# Escorna_CPU_2_10.net
KiCad netlist of a schematic drawn in EAGLE
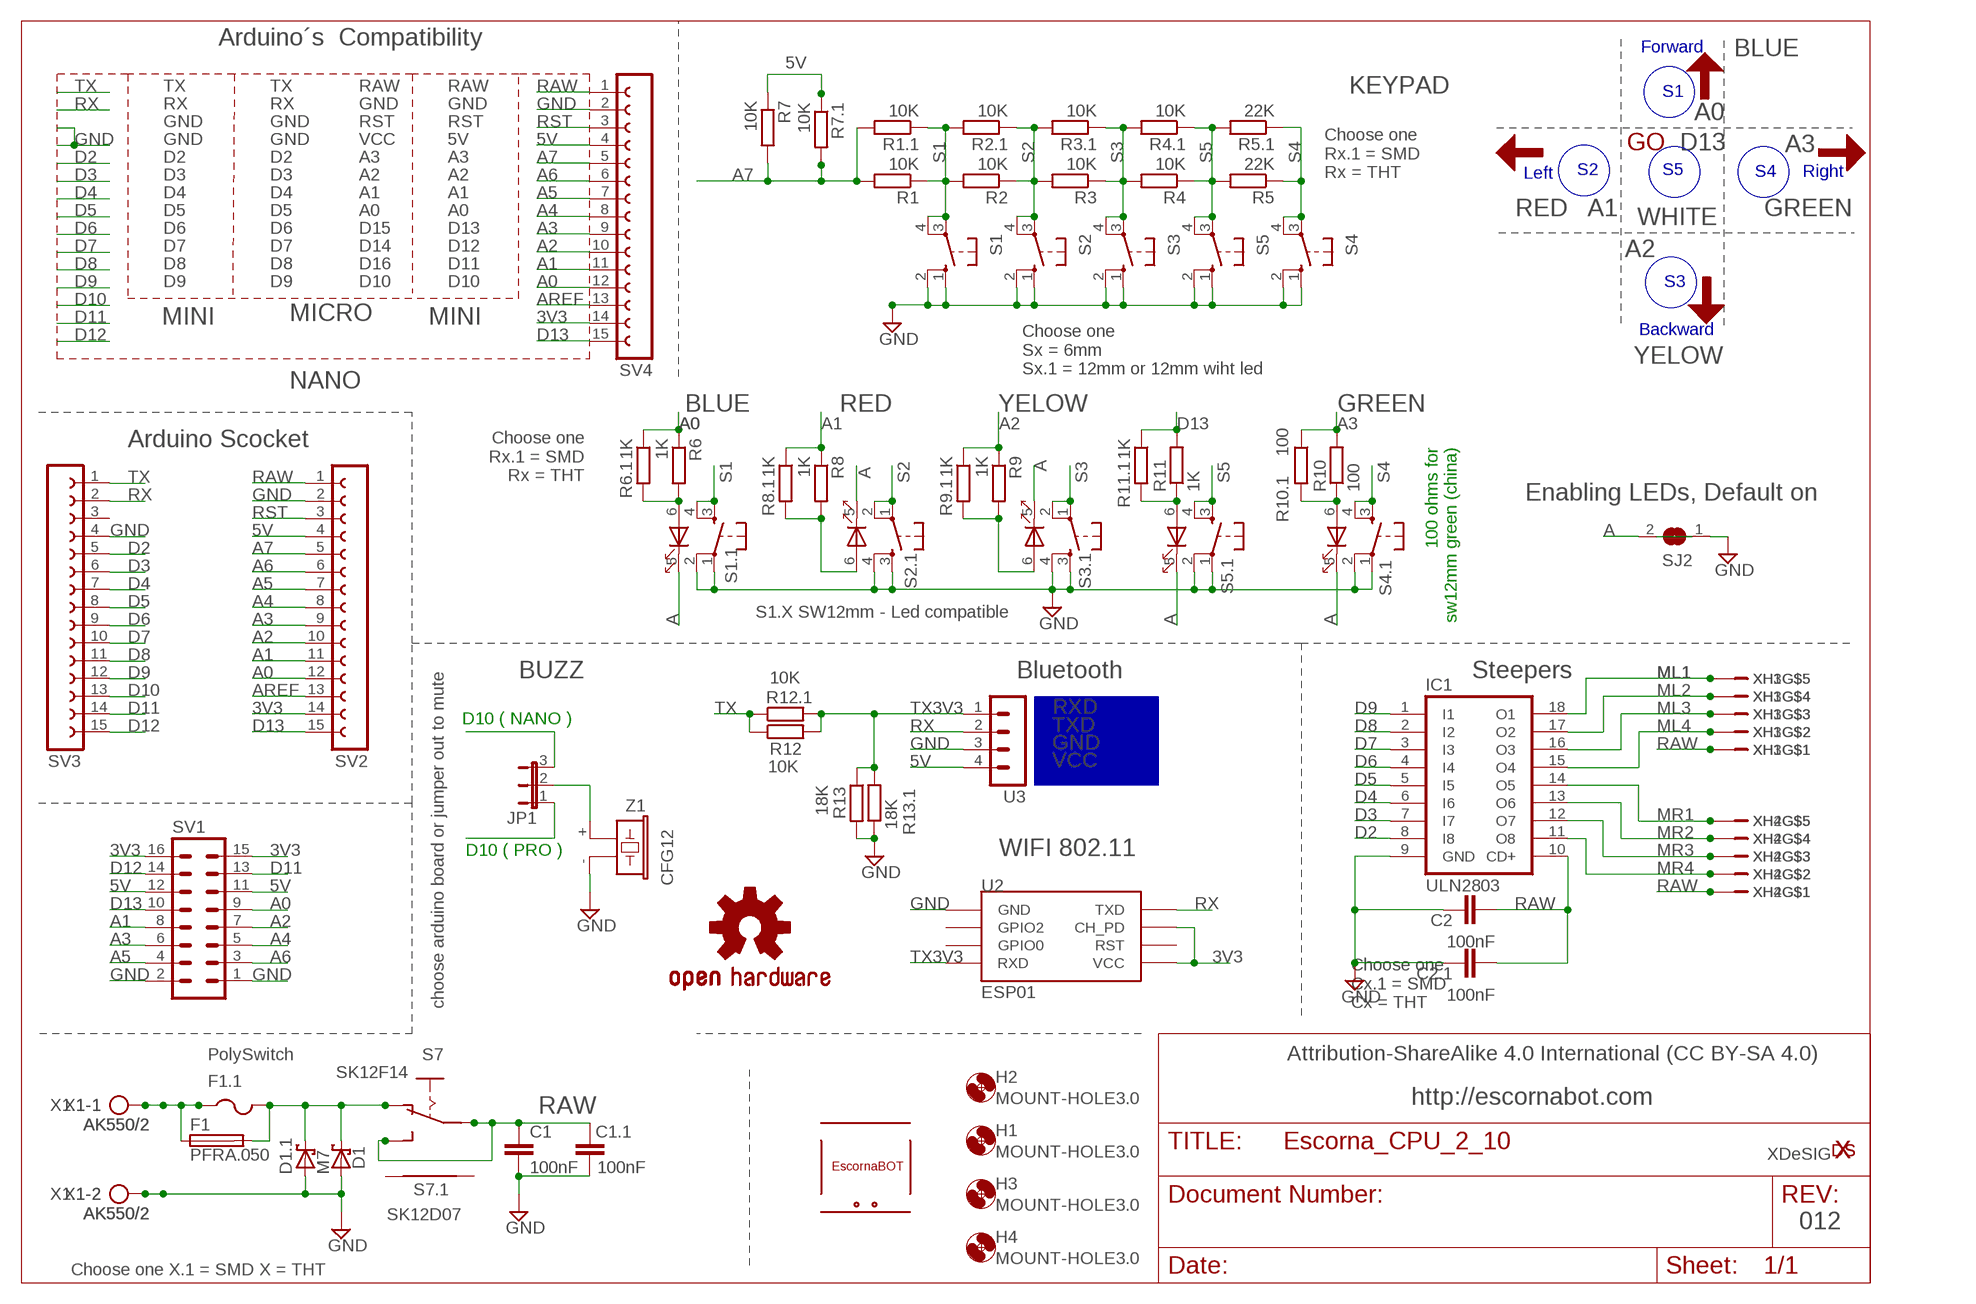
[diagram p0: schematic, sheet 1]

(export (version "E")
  (design (tool "Eeschema 10.0.6"))
  (components
    (comp (ref "C1")
      (value "100nF")
      (footprint "eagle-import:C025-025X050")
      (libsource (lib "eagle-import") (part "C-EU025-025X050"))
    )
    (comp (ref "C1.1")
      (value "100nF")
      (footprint "eagle-import:C1206")
      (libsource (lib "eagle-import") (part "C-EUC1206"))
    )
    (comp (ref "C2")
      (value "100nF")
      (footprint "eagle-import:C025-025X050")
      (libsource (lib "eagle-import") (part "C-EU025-025X050"))
    )
    (comp (ref "C2.1")
      (value "100nF")
      (footprint "eagle-import:C1206")
      (libsource (lib "eagle-import") (part "C-EUC1206"))
    )
    (comp (ref "D1")
      (value "1N5817")
      (footprint "eagle-import:DO41-10")
      (libsource (lib "eagle-import") (part "P4KEXX"))
    )
    (comp (ref "D1.1")
      (value "M7")
      (footprint "eagle-import:SMA")
      (libsource (lib "eagle-import") (part "SCHOTTKY-DIODESMA"))
    )
    (comp (ref "ESC")
      (value "ESCORNABOT")
      (footprint "eagle-import:ESCORNA_PEQUE")
      (libsource (lib "eagle-import") (part "ESCORNABOT"))
    )
    (comp (ref "F1")
      (value "PFRA.050")
      (footprint "eagle-import:TE5")
      (libsource (lib "eagle-import") (part "FUSETE5"))
    )
    (comp (ref "F1.1")
      (value "PolySwitch")
      (footprint "eagle-import:R1206")
      (libsource (lib "eagle-import") (part "PTCFUSE-1206"))
    )
    (comp (ref "H1")
      (value "MOUNT-HOLE3.0")
      (footprint "eagle-import:3,0")
      (libsource (lib "eagle-import") (part "MOUNT-HOLE3.0"))
    )
    (comp (ref "H2")
      (value "MOUNT-HOLE3.0")
      (footprint "eagle-import:3,0")
      (libsource (lib "eagle-import") (part "MOUNT-HOLE3.0"))
    )
    (comp (ref "H3")
      (value "MOUNT-HOLE3.0")
      (footprint "eagle-import:3,0")
      (libsource (lib "eagle-import") (part "MOUNT-HOLE3.0"))
    )
    (comp (ref "H4")
      (value "MOUNT-HOLE3.0")
      (footprint "eagle-import:3,0")
      (libsource (lib "eagle-import") (part "MOUNT-HOLE3.0"))
    )
    (comp (ref "IC1")
      (value "ULN2803")
      (footprint "eagle-import:DIL18")
      (libsource (lib "eagle-import") (part "ULN2803A"))
    )
    (comp (ref "JP1")
      (value "JUMPER_JP2E")
      (footprint "eagle-import:JUMPER_JP2")
      (libsource (lib "eagle-import") (part "JUMPER_JP2E"))
    )
    (comp (ref "LOGO2")
      (value "OSHW-LOGOS")
      (footprint "eagle-import:OSHW-LOGO-S")
      (libsource (lib "eagle-import") (part "OSHW-LOGOS"))
    )
    (comp (ref "R1")
      (value "10K")
      (footprint "eagle-import:0204_7")
      (libsource (lib "eagle-import") (part "R-EU_0204/7"))
    )
    (comp (ref "R1.1")
      (value "10K")
      (footprint "eagle-import:R0603")
      (libsource (lib "eagle-import") (part "R-EU_R0603"))
    )
    (comp (ref "R2")
      (value "10K")
      (footprint "eagle-import:0204_7")
      (libsource (lib "eagle-import") (part "R-EU_0204/7"))
    )
    (comp (ref "R2.1")
      (value "10K")
      (footprint "eagle-import:R0603")
      (libsource (lib "eagle-import") (part "R-EU_R0603"))
    )
    (comp (ref "R3")
      (value "10K")
      (footprint "eagle-import:0204_7")
      (libsource (lib "eagle-import") (part "R-EU_0204/7"))
    )
    (comp (ref "R3.1")
      (value "10K")
      (footprint "eagle-import:R0603")
      (libsource (lib "eagle-import") (part "R-EU_R0603"))
    )
    (comp (ref "R4")
      (value "10K")
      (footprint "eagle-import:0204_7")
      (libsource (lib "eagle-import") (part "R-EU_0204/7"))
    )
    (comp (ref "R4.1")
      (value "10K")
      (footprint "eagle-import:R0603")
      (libsource (lib "eagle-import") (part "R-EU_R0603"))
    )
    (comp (ref "R5")
      (value "22K")
      (footprint "eagle-import:0204_7")
      (libsource (lib "eagle-import") (part "R-EU_0204/7"))
    )
    (comp (ref "R5.1")
      (value "22K")
      (footprint "eagle-import:R0603")
      (libsource (lib "eagle-import") (part "R-EU_R0603"))
    )
    (comp (ref "R6")
      (value "1K")
      (footprint "eagle-import:0204_7")
      (libsource (lib "eagle-import") (part "R-EU_0204/7"))
    )
    (comp (ref "R6.1")
      (value "1K")
      (footprint "eagle-import:R0603")
      (libsource (lib "eagle-import") (part "R-EU_R0603"))
    )
    (comp (ref "R7")
      (value "10K")
      (footprint "eagle-import:0204_7")
      (libsource (lib "eagle-import") (part "R-EU_0204/7"))
    )
    (comp (ref "R7.1")
      (value "10K")
      (footprint "eagle-import:R0603")
      (libsource (lib "eagle-import") (part "R-EU_R0603"))
    )
    (comp (ref "R8")
      (value "1K")
      (footprint "eagle-import:0204_7")
      (libsource (lib "eagle-import") (part "R-EU_0204/7"))
    )
    (comp (ref "R8.1")
      (value "1K")
      (footprint "eagle-import:R0603")
      (libsource (lib "eagle-import") (part "R-EU_R0603"))
    )
    (comp (ref "R9")
      (value "1K")
      (footprint "eagle-import:0204_7")
      (libsource (lib "eagle-import") (part "R-EU_0204/7"))
    )
    (comp (ref "R9.1")
      (value "1K")
      (footprint "eagle-import:R0603")
      (libsource (lib "eagle-import") (part "R-EU_R0603"))
    )
    (comp (ref "R10")
      (value "100")
      (footprint "eagle-import:0204_7")
      (libsource (lib "eagle-import") (part "R-EU_0204/7"))
    )
    (comp (ref "R10.1")
      (value "100")
      (footprint "eagle-import:R0603")
      (libsource (lib "eagle-import") (part "R-EU_R0603"))
    )
    (comp (ref "R11")
      (value "1K")
      (footprint "eagle-import:0204_7")
      (libsource (lib "eagle-import") (part "R-EU_0204/7"))
    )
    (comp (ref "R11.1")
      (value "1K")
      (footprint "eagle-import:R0603")
      (libsource (lib "eagle-import") (part "R-EU_R0603"))
    )
    (comp (ref "R12")
      (value "10K")
      (footprint "eagle-import:0204_7")
      (libsource (lib "eagle-import") (part "R-EU_0204/7"))
    )
    (comp (ref "R12.1")
      (value "10K")
      (footprint "eagle-import:R0603")
      (libsource (lib "eagle-import") (part "R-EU_R0603"))
    )
    (comp (ref "R13")
      (value "18K")
      (footprint "eagle-import:0204_7")
      (libsource (lib "eagle-import") (part "R-EU_0204/7"))
    )
    (comp (ref "R13.1")
      (value "18K")
      (footprint "eagle-import:R0603")
      (libsource (lib "eagle-import") (part "R-EU_R0603"))
    )
    (comp (ref "S1")
      (value "10-XX")
      (footprint "eagle-import:B3F-10XX")
      (fields (field (name "MPN") "B3F-1000"))
      (libsource (lib "eagle-import") (part "10-XX"))
    )
    (comp (ref "S1.1")
      (value "B3F-9XXX")
      (footprint "eagle-import:B3F-9XXX")
      (libsource (lib "eagle-import") (part "SWITCH-OMRON_B3F-9XXX"))
    )
    (comp (ref "S2")
      (value "10-XX")
      (footprint "eagle-import:B3F-10XX")
      (fields (field (name "MPN") "B3F-1000"))
      (libsource (lib "eagle-import") (part "10-XX"))
    )
    (comp (ref "S2.1")
      (value "B3F-9XXX")
      (footprint "eagle-import:B3F-9XXX")
      (libsource (lib "eagle-import") (part "SWITCH-OMRON_B3F-9XXX"))
    )
    (comp (ref "S3")
      (value "10-XX")
      (footprint "eagle-import:B3F-10XX")
      (fields (field (name "MPN") "B3F-1000"))
      (libsource (lib "eagle-import") (part "10-XX"))
    )
    (comp (ref "S3.1")
      (value "B3F-9XXX")
      (footprint "eagle-import:B3F-9XXX")
      (libsource (lib "eagle-import") (part "SWITCH-OMRON_B3F-9XXX"))
    )
    (comp (ref "S4")
      (value "10-XX")
      (footprint "eagle-import:B3F-10XX")
      (fields (field (name "MPN") "B3F-1000"))
      (libsource (lib "eagle-import") (part "10-XX"))
    )
    (comp (ref "S4.1")
      (value "B3F-9XXX")
      (footprint "eagle-import:B3F-9XXX")
      (libsource (lib "eagle-import") (part "SWITCH-OMRON_B3F-9XXX"))
    )
    (comp (ref "S5")
      (value "10-XX")
      (footprint "eagle-import:B3F-10XX")
      (fields (field (name "MPN") "B3F-1000"))
      (libsource (lib "eagle-import") (part "10-XX"))
    )
    (comp (ref "S5.1")
      (value "B3F-9XXX")
      (footprint "eagle-import:B3F-9XXX")
      (libsource (lib "eagle-import") (part "SWITCH-OMRON_B3F-9XXX"))
    )
    (comp (ref "S7")
      (value "SK12F14")
      (footprint "eagle-import:ESCORNA_SK-12F14-G")
      (libsource (lib "eagle-import") (part "ESCORNA_SK12F14F"))
    )
    (comp (ref "S7.1")
      (value "SK12D07")
      (footprint "eagle-import:ESCORNA_SK-12D07")
      (libsource (lib "eagle-import") (part "ESCORNA_SK12F14D"))
    )
    (comp (ref "SJ2") (value "SJ") (footprint "eagle-import:SJ") (libsource (lib "eagle-import") (part "SJ")))
    (comp (ref "SV1")
      (value "MA08-2")
      (footprint "eagle-import:MA08-2")
      (libsource (lib "eagle-import") (part "MA08-2"))
    )
    (comp (ref "SV2")
      (value "CON-LSTA_FE15-1")
      (footprint "eagle-import:CON-LSTA_FE15")
      (libsource (lib "eagle-import") (part "CON-LSTA_FE15-1"))
    )
    (comp (ref "SV3")
      (value "CON-LSTA_FE15-1")
      (footprint "eagle-import:CON-LSTA_FE15")
      (libsource (lib "eagle-import") (part "CON-LSTA_FE15-1"))
    )
    (comp (ref "SV4")
      (value "CON-LSTA_FE15-1")
      (footprint "eagle-import:CON-LSTA_FE15")
      (fields (field (name "OC_FARNELL") "unknown") (field (name "OC_NEWARK") "unknown"))
      (libsource (lib "eagle-import") (part "CON-LSTA_FE15-1"))
    )
    (comp (ref "U$1")
      (value "FRECHA")
      (footprint "eagle-import:FRECHA")
      (libsource (lib "eagle-import") (part "FRECHA"))
    )
    (comp (ref "U$2")
      (value "GO")
      (footprint "eagle-import:VALE")
      (libsource (lib "eagle-import") (part "GO"))
    )
    (comp (ref "U$3")
      (value "FRECHA")
      (footprint "eagle-import:FRECHA")
      (libsource (lib "eagle-import") (part "FRECHA"))
    )
    (comp (ref "U$6")
      (value "FRECHA")
      (footprint "eagle-import:FRECHA")
      (libsource (lib "eagle-import") (part "FRECHA"))
    )
    (comp (ref "U$11")
      (value "FRECHA")
      (footprint "eagle-import:FRECHA")
      (libsource (lib "eagle-import") (part "FRECHA"))
    )
    (comp (ref "U$13")
      (value "XDESIG_XDESIG21")
      (footprint "eagle-import:XDESIG_XDESIG")
      (libsource (lib "eagle-import") (part "XDESIG_XDESIG21"))
    )
    (comp (ref "U2")
      (value "ESP01")
      (footprint "eagle-import:ESP01")
      (libsource (lib "eagle-import") (part "ESP01"))
    )
    (comp (ref "U3")
      (value "MA04-1")
      (footprint "eagle-import:MA04-1")
      (libsource (lib "eagle-import") (part "MA04-1"))
    )
    (comp (ref "X1")
      (value "AK550/2")
      (footprint "eagle-import:AK550_2")
      (libsource (lib "eagle-import") (part "AK550/2"))
    )
    (comp (ref "X1.1")
      (value "AK550/2")
      (footprint "eagle-import:AK550_2")
      (fields (field (name "OC_FARNELL") "unknown") (field (name "OC_NEWARK") "unknown"))
      (libsource (lib "eagle-import") (part "AK550/2"))
    )
    (comp (ref "XDS1")
      (value "XDESIG")
      (footprint "eagle-import:XDESIG_CU_2")
      (libsource (lib "eagle-import") (part "XDESIG"))
    )
    (comp (ref "XH1")
      (value "B5B-XH-A")
      (footprint "eagle-import:B5B-XH-A")
      (libsource (lib "eagle-import") (part "B5B-XH-A"))
    )
    (comp (ref "XH2")
      (value "B5B-XH-A")
      (footprint "eagle-import:B5B-XH-A")
      (libsource (lib "eagle-import") (part "B5B-XH-A"))
    )
    (comp (ref "XH3")
      (value "B5B-XH-A")
      (footprint "eagle-import:B5B-XH-A")
      (libsource (lib "eagle-import") (part "B5B-XH-A"))
    )
    (comp (ref "XH4")
      (value "B5B-XH-A")
      (footprint "eagle-import:B5B-XH-A")
      (libsource (lib "eagle-import") (part "B5B-XH-A"))
    )
    (comp (ref "Z1")
      (value "CFG12")
      (footprint "eagle-import:F_CM12P")
      (libsource (lib "eagle-import") (part "F/CM12P"))
    )
  )
  (nets
    (net (code "1") (name "/3V3") (class "Default")
      (node (ref "SV1") (pin "15") (pinfunction "15_15") (pintype "passive"))
      (node (ref "SV1") (pin "16") (pinfunction "16_16") (pintype "passive"))
      (node (ref "SV2") (pin "14") (pinfunction "14_14") (pintype "passive"))
      (node (ref "SV4") (pin "14") (pinfunction "14_14") (pintype "passive"))
      (node (ref "U2") (pin "CH_PD") (pinfunction "CH_PD_CH_PD") (pintype "bidirectional"))
      (node (ref "U2") (pin "VCC") (pinfunction "VCC_VCC") (pintype "bidirectional"))
    )
    (net (code "2") (name "/5V") (class "Default")
      (node (ref "R7") (pin "1") (pinfunction "1_1") (pintype "passive"))
      (node (ref "R7.1") (pin "1") (pinfunction "1_1") (pintype "passive"))
      (node (ref "SV1") (pin "11") (pinfunction "11_11") (pintype "passive"))
      (node (ref "SV1") (pin "12") (pinfunction "12_12") (pintype "passive"))
      (node (ref "SV2") (pin "4") (pinfunction "4_4") (pintype "passive"))
      (node (ref "SV4") (pin "4") (pinfunction "4_4") (pintype "passive"))
      (node (ref "U3") (pin "4") (pinfunction "4_4") (pintype "passive"))
    )
    (net (code "3") (name "/A") (class "Default")
      (node (ref "S1.1") (pin "5") (pinfunction "K_5") (pintype "passive"))
      (node (ref "S2.1") (pin "5") (pinfunction "K_5") (pintype "passive"))
      (node (ref "S3.1") (pin "5") (pinfunction "K_5") (pintype "passive"))
      (node (ref "S4.1") (pin "5") (pinfunction "K_5") (pintype "passive"))
      (node (ref "S5.1") (pin "5") (pinfunction "K_5") (pintype "passive"))
      (node (ref "SJ2") (pin "2") (pinfunction "2_2") (pintype "passive"))
    )
    (net (code "4") (name "/A0") (class "Default")
      (node (ref "JP1") (pin "1") (pinfunction "1_1") (pintype "passive"))
      (node (ref "R6") (pin "1") (pinfunction "1_1") (pintype "passive"))
      (node (ref "R6.1") (pin "1") (pinfunction "1_1") (pintype "passive"))
      (node (ref "SV1") (pin "9") (pinfunction "9_9") (pintype "passive"))
      (node (ref "SV2") (pin "12") (pinfunction "12_12") (pintype "passive"))
      (node (ref "SV4") (pin "12") (pinfunction "12_12") (pintype "passive"))
    )
    (net (code "5") (name "/A1") (class "Default")
      (node (ref "R8") (pin "1") (pinfunction "1_1") (pintype "passive"))
      (node (ref "R8.1") (pin "1") (pinfunction "1_1") (pintype "passive"))
      (node (ref "SV1") (pin "8") (pinfunction "8_8") (pintype "passive"))
      (node (ref "SV2") (pin "11") (pinfunction "11_11") (pintype "passive"))
      (node (ref "SV4") (pin "11") (pinfunction "11_11") (pintype "passive"))
    )
    (net (code "6") (name "/A2") (class "Default")
      (node (ref "R9") (pin "1") (pinfunction "1_1") (pintype "passive"))
      (node (ref "R9.1") (pin "1") (pinfunction "1_1") (pintype "passive"))
      (node (ref "SV1") (pin "7") (pinfunction "7_7") (pintype "passive"))
      (node (ref "SV2") (pin "10") (pinfunction "10_10") (pintype "passive"))
      (node (ref "SV4") (pin "10") (pinfunction "10_10") (pintype "passive"))
    )
    (net (code "7") (name "/A3") (class "Default")
      (node (ref "R10") (pin "2") (pinfunction "2_2") (pintype "passive"))
      (node (ref "R10.1") (pin "1") (pinfunction "1_1") (pintype "passive"))
      (node (ref "SV1") (pin "6") (pinfunction "6_6") (pintype "passive"))
      (node (ref "SV2") (pin "9") (pinfunction "9_9") (pintype "passive"))
      (node (ref "SV4") (pin "9") (pinfunction "9_9") (pintype "passive"))
    )
    (net (code "8") (name "/A4") (class "Default")
      (node (ref "SV1") (pin "5") (pinfunction "5_5") (pintype "passive"))
      (node (ref "SV2") (pin "8") (pinfunction "8_8") (pintype "passive"))
      (node (ref "SV4") (pin "8") (pinfunction "8_8") (pintype "passive"))
    )
    (net (code "9") (name "/A5") (class "Default")
      (node (ref "SV1") (pin "4") (pinfunction "4_4") (pintype "passive"))
      (node (ref "SV2") (pin "7") (pinfunction "7_7") (pintype "passive"))
      (node (ref "SV4") (pin "7") (pinfunction "7_7") (pintype "passive"))
    )
    (net (code "10") (name "/A6") (class "Default")
      (node (ref "SV1") (pin "3") (pinfunction "3_3") (pintype "passive"))
      (node (ref "SV2") (pin "6") (pinfunction "6_6") (pintype "passive"))
      (node (ref "SV4") (pin "6") (pinfunction "6_6") (pintype "passive"))
    )
    (net (code "11") (name "/A7") (class "Default")
      (node (ref "R1") (pin "2") (pinfunction "2_2") (pintype "passive"))
      (node (ref "R1.1") (pin "2") (pinfunction "2_2") (pintype "passive"))
      (node (ref "R7") (pin "2") (pinfunction "2_2") (pintype "passive"))
      (node (ref "R7.1") (pin "2") (pinfunction "2_2") (pintype "passive"))
      (node (ref "SV2") (pin "5") (pinfunction "5_5") (pintype "passive"))
      (node (ref "SV4") (pin "5") (pinfunction "5_5") (pintype "passive"))
    )
    (net (code "12") (name "/AREF") (class "Default")
      (node (ref "SV2") (pin "13") (pinfunction "13_13") (pintype "passive"))
      (node (ref "SV4") (pin "13") (pinfunction "13_13") (pintype "passive"))
    )
    (net (code "13") (name "/D2") (class "Default")
      (node (ref "IC1") (pin "8") (pinfunction "I8_8") (pintype "input"))
      (node (ref "SV3") (pin "5") (pinfunction "5_5") (pintype "passive"))
    )
    (net (code "14") (name "/D3") (class "Default")
      (node (ref "IC1") (pin "7") (pinfunction "I7_7") (pintype "input"))
      (node (ref "SV3") (pin "6") (pinfunction "6_6") (pintype "passive"))
    )
    (net (code "15") (name "/D4") (class "Default")
      (node (ref "IC1") (pin "6") (pinfunction "I6_6") (pintype "input"))
      (node (ref "SV3") (pin "7") (pinfunction "7_7") (pintype "passive"))
    )
    (net (code "16") (name "/D5") (class "Default")
      (node (ref "IC1") (pin "5") (pinfunction "I5_5") (pintype "input"))
      (node (ref "SV3") (pin "8") (pinfunction "8_8") (pintype "passive"))
    )
    (net (code "17") (name "/D6") (class "Default")
      (node (ref "IC1") (pin "4") (pinfunction "I4_4") (pintype "input"))
      (node (ref "SV3") (pin "9") (pinfunction "9_9") (pintype "passive"))
    )
    (net (code "18") (name "/D7") (class "Default")
      (node (ref "IC1") (pin "3") (pinfunction "I3_3") (pintype "input"))
      (node (ref "SV3") (pin "10") (pinfunction "10_10") (pintype "passive"))
    )
    (net (code "19") (name "/D8") (class "Default")
      (node (ref "IC1") (pin "2") (pinfunction "I2_2") (pintype "input"))
      (node (ref "SV3") (pin "11") (pinfunction "11_11") (pintype "passive"))
    )
    (net (code "20") (name "/D9") (class "Default")
      (node (ref "IC1") (pin "1") (pinfunction "I1_1") (pintype "input"))
      (node (ref "SV3") (pin "12") (pinfunction "12_12") (pintype "passive"))
    )
    (net (code "21") (name "/D10") (class "Default")
      (node (ref "JP1") (pin "3") (pinfunction "3_3") (pintype "passive"))
      (node (ref "SV3") (pin "13") (pinfunction "13_13") (pintype "passive"))
    )
    (net (code "22") (name "/D11") (class "Default")
      (node (ref "SV1") (pin "13") (pinfunction "13_13") (pintype "passive"))
      (node (ref "SV3") (pin "14") (pinfunction "14_14") (pintype "passive"))
    )
    (net (code "23") (name "/D12") (class "Default")
      (node (ref "SV1") (pin "14") (pinfunction "14_14") (pintype "passive"))
      (node (ref "SV3") (pin "15") (pinfunction "15_15") (pintype "passive"))
    )
    (net (code "24") (name "/D13") (class "Default")
      (node (ref "R11") (pin "2") (pinfunction "2_2") (pintype "passive"))
      (node (ref "R11.1") (pin "1") (pinfunction "1_1") (pintype "passive"))
      (node (ref "SV1") (pin "10") (pinfunction "10_10") (pintype "passive"))
      (node (ref "SV2") (pin "15") (pinfunction "15_15") (pintype "passive"))
      (node (ref "SV4") (pin "15") (pinfunction "15_15") (pintype "passive"))
    )
    (net (code "25") (name "/ML1") (class "Default")
      (node (ref "IC1") (pin "18") (pinfunction "O1_18") (pintype "open_collector"))
      (node (ref "XH1") (pin "P$5") (pinfunction "1_P$5") (pintype "passive"))
      (node (ref "XH3") (pin "P$5") (pinfunction "1_P$5") (pintype "passive"))
    )
    (net (code "26") (name "/ML2") (class "Default")
      (node (ref "IC1") (pin "17") (pinfunction "O2_17") (pintype "open_collector"))
      (node (ref "XH1") (pin "P$4") (pinfunction "1_P$4") (pintype "passive"))
      (node (ref "XH3") (pin "P$4") (pinfunction "1_P$4") (pintype "passive"))
    )
    (net (code "27") (name "/ML3") (class "Default")
      (node (ref "IC1") (pin "16") (pinfunction "O3_16") (pintype "open_collector"))
      (node (ref "XH1") (pin "P$3") (pinfunction "1_P$3") (pintype "passive"))
      (node (ref "XH3") (pin "P$3") (pinfunction "1_P$3") (pintype "passive"))
    )
    (net (code "28") (name "/ML4") (class "Default")
      (node (ref "IC1") (pin "15") (pinfunction "O4_15") (pintype "open_collector"))
      (node (ref "XH1") (pin "P$2") (pinfunction "1_P$2") (pintype "passive"))
      (node (ref "XH3") (pin "P$2") (pinfunction "1_P$2") (pintype "passive"))
    )
    (net (code "29") (name "/MR1") (class "Default")
      (node (ref "IC1") (pin "14") (pinfunction "O5_14") (pintype "open_collector"))
      (node (ref "XH2") (pin "P$5") (pinfunction "1_P$5") (pintype "passive"))
      (node (ref "XH4") (pin "P$5") (pinfunction "1_P$5") (pintype "passive"))
    )
    (net (code "30") (name "/MR2") (class "Default")
      (node (ref "IC1") (pin "13") (pinfunction "O6_13") (pintype "open_collector"))
      (node (ref "XH2") (pin "P$4") (pinfunction "1_P$4") (pintype "passive"))
      (node (ref "XH4") (pin "P$4") (pinfunction "1_P$4") (pintype "passive"))
    )
    (net (code "31") (name "/MR3") (class "Default")
      (node (ref "IC1") (pin "12") (pinfunction "O7_12") (pintype "open_collector"))
      (node (ref "XH2") (pin "P$3") (pinfunction "1_P$3") (pintype "passive"))
      (node (ref "XH4") (pin "P$3") (pinfunction "1_P$3") (pintype "passive"))
    )
    (net (code "32") (name "/MR4") (class "Default")
      (node (ref "IC1") (pin "11") (pinfunction "O8_11") (pintype "open_collector"))
      (node (ref "XH2") (pin "P$2") (pinfunction "1_P$2") (pintype "passive"))
      (node (ref "XH4") (pin "P$2") (pinfunction "1_P$2") (pintype "passive"))
    )
    (net (code "33") (name "/RAW") (class "Default")
      (node (ref "C1") (pin "1") (pinfunction "1_1") (pintype "passive"))
      (node (ref "C1.1") (pin "2") (pinfunction "2_2") (pintype "passive"))
      (node (ref "C2") (pin "2") (pinfunction "2_2") (pintype "passive"))
      (node (ref "C2.1") (pin "2") (pinfunction "2_2") (pintype "passive"))
      (node (ref "IC1") (pin "10") (pinfunction "CD+_10") (pintype "passive"))
      (node (ref "S7") (pin "P$1") (pinfunction "P_P$1") (pintype "passive"))
      (node (ref "S7") (pin "P$3") (pinfunction "S_P$3") (pintype "passive"))
      (node (ref "S7.1") (pin "P$1") (pinfunction "P_P$1") (pintype "passive"))
      (node (ref "S7.1") (pin "P$3") (pinfunction "S_P$3") (pintype "passive"))
      (node (ref "SV2") (pin "1") (pinfunction "1_1") (pintype "passive"))
      (node (ref "SV4") (pin "1") (pinfunction "1_1") (pintype "passive"))
      (node (ref "XH1") (pin "P$1") (pinfunction "1_P$1") (pintype "passive"))
      (node (ref "XH2") (pin "P$1") (pinfunction "1_P$1") (pintype "passive"))
      (node (ref "XH3") (pin "P$1") (pinfunction "1_P$1") (pintype "passive"))
      (node (ref "XH4") (pin "P$1") (pinfunction "1_P$1") (pintype "passive"))
    )
    (net (code "34") (name "/RST") (class "Default")
      (node (ref "SV2") (pin "3") (pinfunction "3_3") (pintype "passive"))
      (node (ref "SV4") (pin "3") (pinfunction "3_3") (pintype "passive"))
    )
    (net (code "35") (name "/RX") (class "Default")
      (node (ref "SV3") (pin "2") (pinfunction "2_2") (pintype "passive"))
      (node (ref "U2") (pin "TX") (pinfunction "TXD_TX") (pintype "bidirectional"))
      (node (ref "U3") (pin "2") (pinfunction "2_2") (pintype "passive"))
    )
    (net (code "36") (name "/S1") (class "Default")
      (node (ref "R1") (pin "1") (pinfunction "1_1") (pintype "passive"))
      (node (ref "R1.1") (pin "1") (pinfunction "1_1") (pintype "passive"))
      (node (ref "R2") (pin "2") (pinfunction "2_2") (pintype "passive"))
      (node (ref "R2.1") (pin "2") (pinfunction "2_2") (pintype "passive"))
      (node (ref "S1") (pin "3") (pinfunction "P_3") (pintype "passive"))
      (node (ref "S1") (pin "4") (pinfunction "P1_4") (pintype "passive"))
      (node (ref "S1.1") (pin "3") (pinfunction "S_3") (pintype "passive"))
      (node (ref "S1.1") (pin "4") (pinfunction "S1_4") (pintype "passive"))
    )
    (net (code "37") (name "/S2") (class "Default")
      (node (ref "R2") (pin "1") (pinfunction "1_1") (pintype "passive"))
      (node (ref "R2.1") (pin "1") (pinfunction "1_1") (pintype "passive"))
      (node (ref "R3") (pin "2") (pinfunction "2_2") (pintype "passive"))
      (node (ref "R3.1") (pin "2") (pinfunction "2_2") (pintype "passive"))
      (node (ref "S2") (pin "3") (pinfunction "P_3") (pintype "passive"))
      (node (ref "S2") (pin "4") (pinfunction "P1_4") (pintype "passive"))
      (node (ref "S2.1") (pin "1") (pinfunction "P_1") (pintype "passive"))
      (node (ref "S2.1") (pin "2") (pinfunction "P1_2") (pintype "passive"))
    )
    (net (code "38") (name "/S3") (class "Default")
      (node (ref "R3") (pin "1") (pinfunction "1_1") (pintype "passive"))
      (node (ref "R3.1") (pin "1") (pinfunction "1_1") (pintype "passive"))
      (node (ref "R4") (pin "2") (pinfunction "2_2") (pintype "passive"))
      (node (ref "R4.1") (pin "2") (pinfunction "2_2") (pintype "passive"))
      (node (ref "S3") (pin "3") (pinfunction "P_3") (pintype "passive"))
      (node (ref "S3") (pin "4") (pinfunction "P1_4") (pintype "passive"))
      (node (ref "S3.1") (pin "1") (pinfunction "P_1") (pintype "passive"))
      (node (ref "S3.1") (pin "2") (pinfunction "P1_2") (pintype "passive"))
    )
    (net (code "39") (name "/S4") (class "Default")
      (node (ref "R5") (pin "1") (pinfunction "1_1") (pintype "passive"))
      (node (ref "R5.1") (pin "1") (pinfunction "1_1") (pintype "passive"))
      (node (ref "S4") (pin "3") (pinfunction "P_3") (pintype "passive"))
      (node (ref "S4") (pin "4") (pinfunction "P1_4") (pintype "passive"))
      (node (ref "S4.1") (pin "3") (pinfunction "S_3") (pintype "passive"))
      (node (ref "S4.1") (pin "4") (pinfunction "S1_4") (pintype "passive"))
    )
    (net (code "40") (name "/S5") (class "Default")
      (node (ref "R4") (pin "1") (pinfunction "1_1") (pintype "passive"))
      (node (ref "R4.1") (pin "1") (pinfunction "1_1") (pintype "passive"))
      (node (ref "R5") (pin "2") (pinfunction "2_2") (pintype "passive"))
      (node (ref "R5.1") (pin "2") (pinfunction "2_2") (pintype "passive"))
      (node (ref "S5") (pin "3") (pinfunction "P_3") (pintype "passive"))
      (node (ref "S5") (pin "4") (pinfunction "P1_4") (pintype "passive"))
      (node (ref "S5.1") (pin "3") (pinfunction "S_3") (pintype "passive"))
      (node (ref "S5.1") (pin "4") (pinfunction "S1_4") (pintype "passive"))
    )
    (net (code "41") (name "/TX") (class "Default")
      (node (ref "R12") (pin "1") (pinfunction "1_1") (pintype "passive"))
      (node (ref "R12.1") (pin "1") (pinfunction "1_1") (pintype "passive"))
      (node (ref "SV3") (pin "1") (pinfunction "1_1") (pintype "passive"))
    )
    (net (code "42") (name "/TX3V3") (class "Default")
      (node (ref "R12") (pin "2") (pinfunction "2_2") (pintype "passive"))
      (node (ref "R12.1") (pin "2") (pinfunction "2_2") (pintype "passive"))
      (node (ref "R13") (pin "1") (pinfunction "1_1") (pintype "passive"))
      (node (ref "R13.1") (pin "2") (pinfunction "2_2") (pintype "passive"))
      (node (ref "U2") (pin "RX") (pinfunction "RXD_RX") (pintype "bidirectional"))
      (node (ref "U3") (pin "1") (pinfunction "1_1") (pintype "passive"))
    )
    (net (code "43") (name "GND") (class "Default")
      (node (ref "C1") (pin "2") (pinfunction "2_2") (pintype "passive"))
      (node (ref "C1.1") (pin "1") (pinfunction "1_1") (pintype "passive"))
      (node (ref "C2") (pin "1") (pinfunction "1_1") (pintype "passive"))
      (node (ref "C2.1") (pin "1") (pinfunction "1_1") (pintype "passive"))
      (node (ref "D1") (pin "A") (pinfunction "A_A") (pintype "passive"))
      (node (ref "D1.1") (pin "A") (pinfunction "A_A") (pintype "passive"))
      (node (ref "IC1") (pin "9") (pinfunction "GND_9") (pintype "power_in"))
      (node (ref "R13") (pin "2") (pinfunction "2_2") (pintype "passive"))
      (node (ref "R13.1") (pin "1") (pinfunction "1_1") (pintype "passive"))
      (node (ref "S1") (pin "1") (pinfunction "S_1") (pintype "passive"))
      (node (ref "S1") (pin "2") (pinfunction "S1_2") (pintype "passive"))
      (node (ref "S1.1") (pin "1") (pinfunction "P_1") (pintype "passive"))
      (node (ref "S1.1") (pin "2") (pinfunction "P1_2") (pintype "passive"))
      (node (ref "S2") (pin "1") (pinfunction "S_1") (pintype "passive"))
      (node (ref "S2") (pin "2") (pinfunction "S1_2") (pintype "passive"))
      (node (ref "S2.1") (pin "3") (pinfunction "S_3") (pintype "passive"))
      (node (ref "S2.1") (pin "4") (pinfunction "S1_4") (pintype "passive"))
      (node (ref "S3") (pin "1") (pinfunction "S_1") (pintype "passive"))
      (node (ref "S3") (pin "2") (pinfunction "S1_2") (pintype "passive"))
      (node (ref "S3.1") (pin "3") (pinfunction "S_3") (pintype "passive"))
      (node (ref "S3.1") (pin "4") (pinfunction "S1_4") (pintype "passive"))
      (node (ref "S4") (pin "1") (pinfunction "S_1") (pintype "passive"))
      (node (ref "S4") (pin "2") (pinfunction "S1_2") (pintype "passive"))
      (node (ref "S4.1") (pin "1") (pinfunction "P_1") (pintype "passive"))
      (node (ref "S4.1") (pin "2") (pinfunction "P1_2") (pintype "passive"))
      (node (ref "S5") (pin "1") (pinfunction "S_1") (pintype "passive"))
      (node (ref "S5") (pin "2") (pinfunction "S1_2") (pintype "passive"))
      (node (ref "S5.1") (pin "1") (pinfunction "P_1") (pintype "passive"))
      (node (ref "S5.1") (pin "2") (pinfunction "P1_2") (pintype "passive"))
      (node (ref "SJ2") (pin "1") (pinfunction "1_1") (pintype "passive"))
      (node (ref "SV1") (pin "1") (pinfunction "1_1") (pintype "passive"))
      (node (ref "SV1") (pin "2") (pinfunction "2_2") (pintype "passive"))
      (node (ref "SV2") (pin "2") (pinfunction "2_2") (pintype "passive"))
      (node (ref "SV3") (pin "4") (pinfunction "4_4") (pintype "passive"))
      (node (ref "SV4") (pin "2") (pinfunction "2_2") (pintype "passive"))
      (node (ref "U2") (pin "GND") (pinfunction "GND_GND") (pintype "bidirectional"))
      (node (ref "U3") (pin "3") (pinfunction "3_3") (pintype "passive"))
      (node (ref "X1") (pin "2") (pinfunction "KL_2") (pintype "passive"))
      (node (ref "X1.1") (pin "2") (pinfunction "KL_2") (pintype "passive"))
      (node (ref "Z1") (pin "-") (pinfunction "2_-") (pintype "passive"))
    )
    (net (code "44") (name "Net-(S1.1-A)") (class "Default")
      (node (ref "R6") (pin "2") (pinfunction "2_2") (pintype "passive"))
      (node (ref "R6.1") (pin "2") (pinfunction "2_2") (pintype "passive"))
      (node (ref "S1.1") (pin "6") (pinfunction "A_6") (pintype "passive"))
    )
    (net (code "45") (name "Net-(S2.1-A)") (class "Default")
      (node (ref "R8") (pin "2") (pinfunction "2_2") (pintype "passive"))
      (node (ref "R8.1") (pin "2") (pinfunction "2_2") (pintype "passive"))
      (node (ref "S2.1") (pin "6") (pinfunction "A_6") (pintype "passive"))
    )
    (net (code "46") (name "Net-(S3.1-A)") (class "Default")
      (node (ref "R9") (pin "2") (pinfunction "2_2") (pintype "passive"))
      (node (ref "R9.1") (pin "2") (pinfunction "2_2") (pintype "passive"))
      (node (ref "S3.1") (pin "6") (pinfunction "A_6") (pintype "passive"))
    )
    (net (code "47") (name "Net-(S4.1-A)") (class "Default")
      (node (ref "R10") (pin "1") (pinfunction "1_1") (pintype "passive"))
      (node (ref "R10.1") (pin "2") (pinfunction "2_2") (pintype "passive"))
      (node (ref "S4.1") (pin "6") (pinfunction "A_6") (pintype "passive"))
    )
    (net (code "48") (name "Net-(S5.1-A)") (class "Default")
      (node (ref "R11") (pin "1") (pinfunction "1_1") (pintype "passive"))
      (node (ref "R11.1") (pin "2") (pinfunction "2_2") (pintype "passive"))
      (node (ref "S5.1") (pin "6") (pinfunction "A_6") (pintype "passive"))
    )
    (net (code "49") (name "Net-(S7-O)") (class "Default")
      (node (ref "D1") (pin "C") (pinfunction "C_C") (pintype "passive"))
      (node (ref "D1.1") (pin "C") (pinfunction "C_C") (pintype "passive"))
      (node (ref "F1") (pin "2") (pinfunction "2_2") (pintype "passive"))
      (node (ref "F1.1") (pin "2") (pinfunction "2_2") (pintype "passive"))
      (node (ref "S7") (pin "P$2") (pinfunction "O_P$2") (pintype "passive"))
      (node (ref "S7.1") (pin "P$2") (pinfunction "O_P$2") (pintype "passive"))
    )
    (net (code "50") (name "Net-(S7-P$1)") (class "Default")
      (node (ref "S7") (pin "P$4") (pinfunction "P$1_P$4") (pintype "passive"))
      (node (ref "S7.1") (pin "P$4") (pinfunction "P$1_P$4") (pintype "passive"))
    )
    (net (code "51") (name "Net-(S7-P$2)") (class "Default")
      (node (ref "S7") (pin "P$5") (pinfunction "P$2_P$5") (pintype "bidirectional"))
      (node (ref "S7.1") (pin "P$5") (pinfunction "P$2_P$5") (pintype "bidirectional"))
    )
    (net (code "52") (name "Net-(X1.1A-KL)") (class "Default")
      (node (ref "F1") (pin "1") (pinfunction "1_1") (pintype "passive"))
      (node (ref "F1.1") (pin "1") (pinfunction "1_1") (pintype "passive"))
      (node (ref "X1") (pin "1") (pinfunction "KL_1") (pintype "passive"))
      (node (ref "X1.1") (pin "1") (pinfunction "KL_1") (pintype "passive"))
    )
    (net (code "53") (name "Net-(Z1-1)") (class "Default")
      (node (ref "JP1") (pin "2") (pinfunction "2_2") (pintype "passive"))
      (node (ref "Z1") (pin "+") (pinfunction "1_+") (pintype "passive"))
    )
    (net (code "54") (name "unconnected-(SV3-Pad3)") (class "Default")
      (node (ref "SV3") (pin "3") (pinfunction "3_3") (pintype "passive"))
    )
    (net (code "55") (name "unconnected-(U2-PadGPIO0)") (class "Default")
      (node (ref "U2") (pin "GPIO0") (pinfunction "GPIO0_GPIO0") (pintype "bidirectional"))
    )
    (net (code "56") (name "unconnected-(U2-PadGPIO2)") (class "Default")
      (node (ref "U2") (pin "GPIO2") (pinfunction "GPIO2_GPIO2") (pintype "bidirectional"))
    )
    (net (code "57") (name "unconnected-(U2-PadRST)") (class "Default")
      (node (ref "U2") (pin "RST") (pinfunction "RST_RST") (pintype "bidirectional"))
    )
  )
)
